# Page04_CPU_PWR.net
KiCad netlist of a schematic drawn in Altium Designer
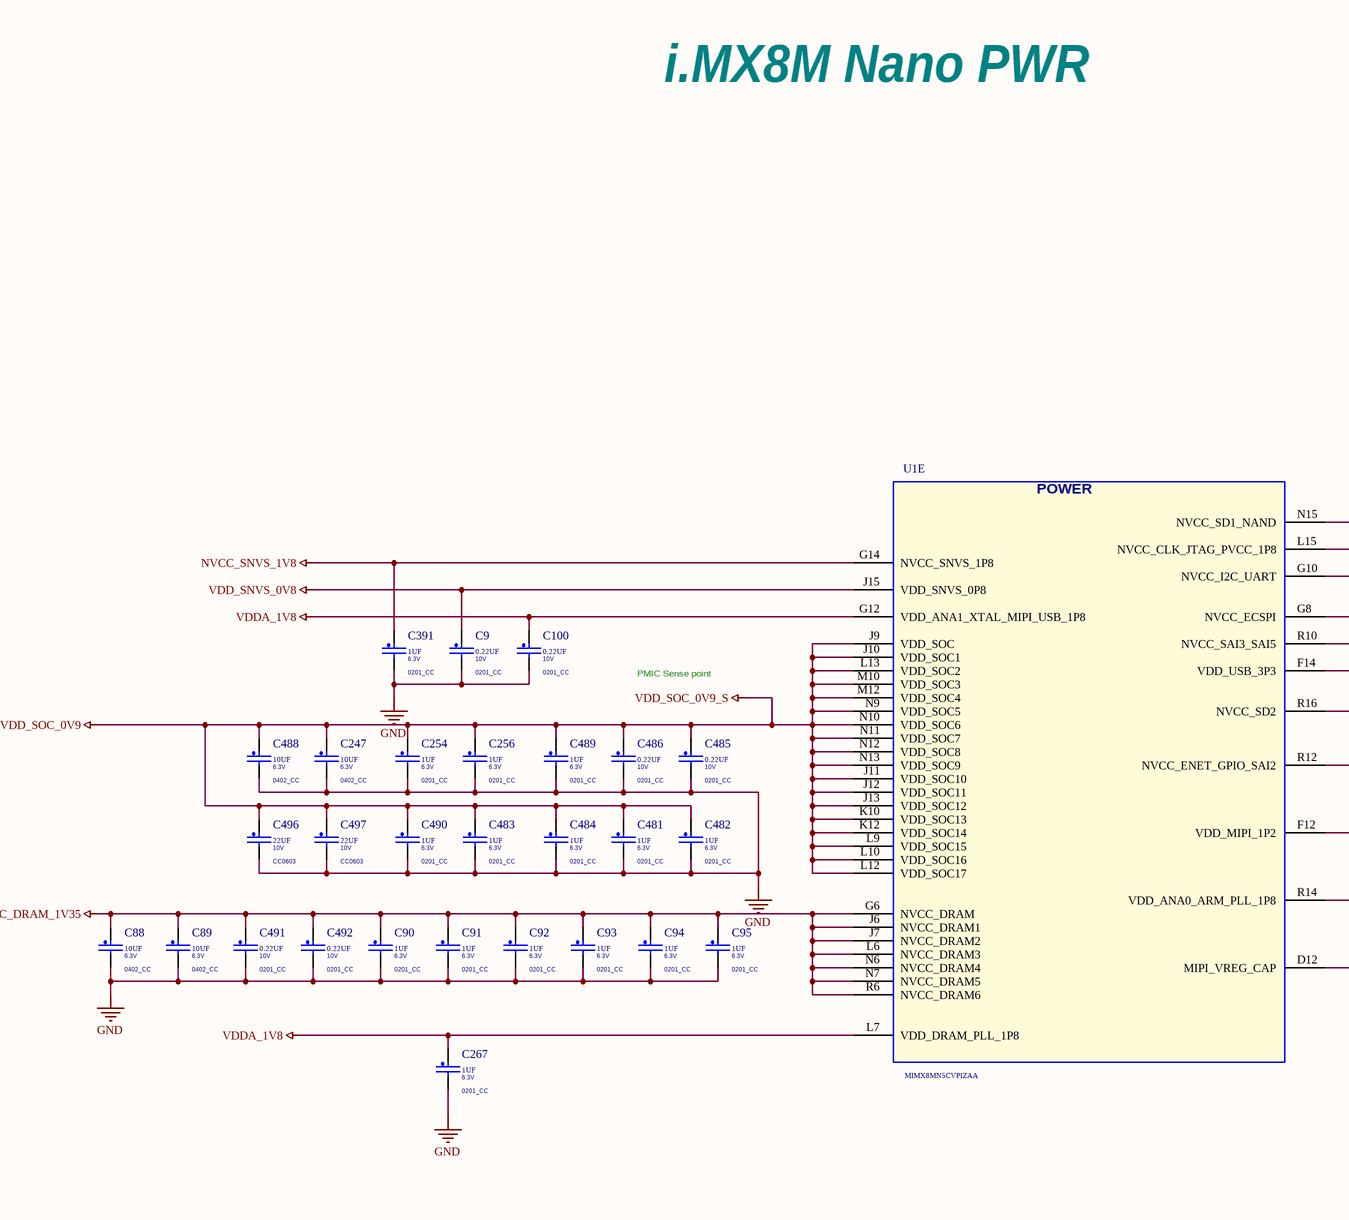
[diagram p0: Page04 CPU PWR.SchDoc, left]
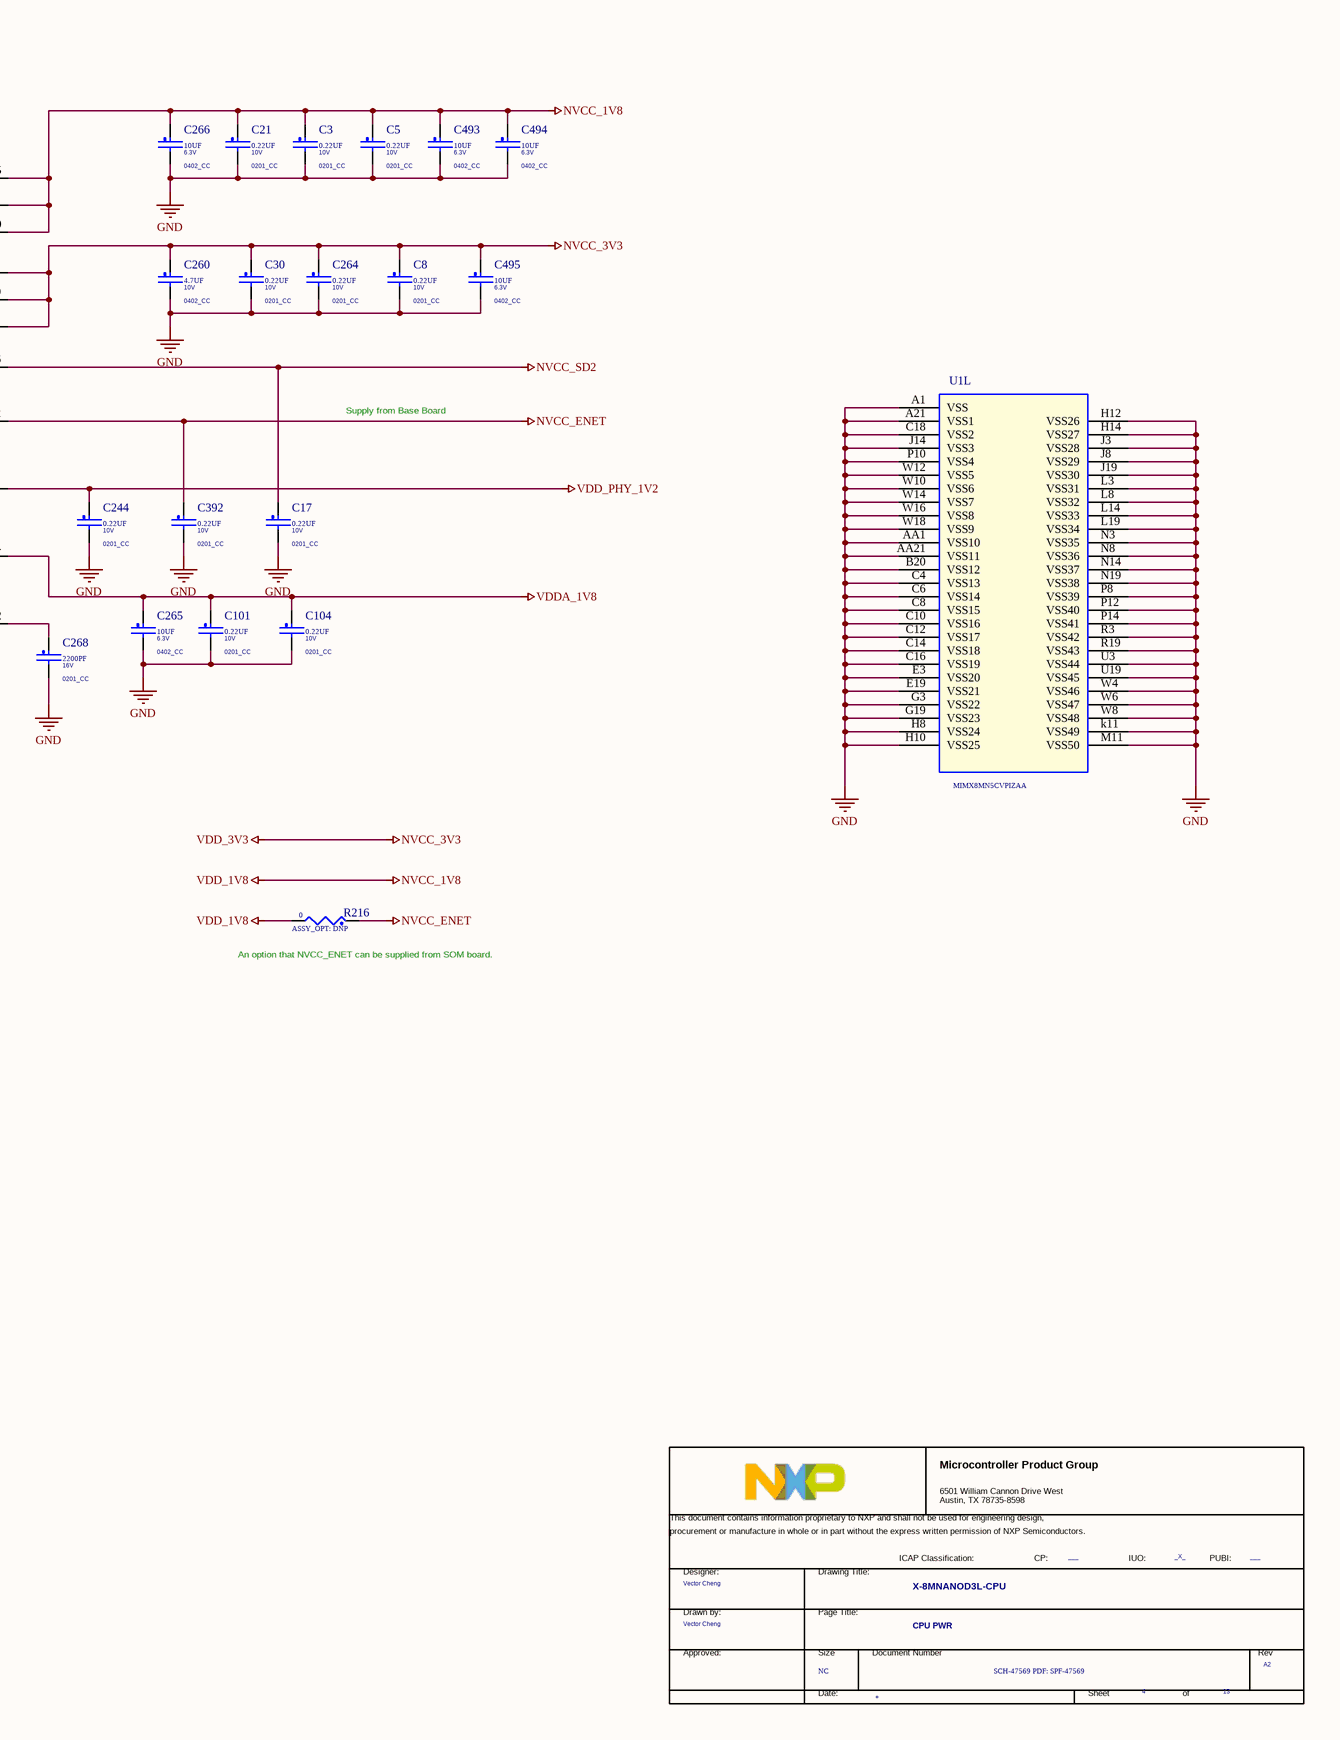
[diagram p1: Page04 CPU PWR.SchDoc, right]

(export (version "E")
  (design (tool "Eeschema 10.0.6"))
  (components
    (comp (ref "C3")
      (value "0.22UF")
      (footprint "0201_CC - C")
      (description "CAP CER 0.22UF 10V 20% X5R 0201")
      (fields
        (field (name "VOLTAGE") "10V")
        (field (name "TOLERANCE") "20%")
        (field (name "PCB FOOTPRINT") "0201_CC")
      )
      (libsource (lib "*") (part "CAP_NP"))
    )
    (comp (ref "C5")
      (value "0.22UF")
      (footprint "0201_CC - C")
      (description "CAP CER 0.22UF 10V 20% X5R 0201")
      (fields
        (field (name "TOLERANCE") "20%")
        (field (name "VOLTAGE") "10V")
        (field (name "PCB FOOTPRINT") "0201_CC")
      )
      (libsource (lib "*") (part "CAP_NP"))
    )
    (comp (ref "C8")
      (value "0.22UF")
      (footprint "0201_CC - C")
      (description "CAP CER 0.22UF 10V 20% X5R 0201")
      (fields
        (field (name "TOLERANCE") "20%")
        (field (name "VOLTAGE") "10V")
        (field (name "PCB FOOTPRINT") "0201_CC")
      )
      (libsource (lib "*") (part "CAP_NP"))
    )
    (comp (ref "C9")
      (value "0.22UF")
      (footprint "0201_CC - C")
      (description "CAP CER 0.22UF 10V 20% X5R 0201")
      (fields
        (field (name "VOLTAGE") "10V")
        (field (name "TOLERANCE") "20%")
        (field (name "PCB FOOTPRINT") "0201_CC")
      )
      (libsource (lib "*") (part "CAP_NP"))
    )
    (comp (ref "C17")
      (value "0.22UF")
      (footprint "0201_CC - C")
      (description "CAP CER 0.22UF 10V 20% X5R 0201")
      (fields
        (field (name "TOLERANCE") "20%")
        (field (name "VOLTAGE") "10V")
        (field (name "PCB FOOTPRINT") "0201_CC")
      )
      (libsource (lib "*") (part "CAP_NP"))
    )
    (comp (ref "C21")
      (value "0.22UF")
      (footprint "0201_CC - C")
      (description "CAP CER 0.22UF 10V 20% X5R 0201")
      (fields
        (field (name "TOLERANCE") "20%")
        (field (name "VOLTAGE") "10V")
        (field (name "PCB FOOTPRINT") "0201_CC")
      )
      (libsource (lib "*") (part "CAP_NP"))
    )
    (comp (ref "C30")
      (value "0.22UF")
      (footprint "0201_CC - C")
      (description "CAP CER 0.22UF 10V 20% X5R 0201")
      (fields
        (field (name "VOLTAGE") "10V")
        (field (name "TOLERANCE") "20%")
        (field (name "PCB FOOTPRINT") "0201_CC")
      )
      (libsource (lib "*") (part "CAP_NP"))
    )
    (comp (ref "C88")
      (value "10UF")
      (footprint "0402_CC - C")
      (description "CAP CER 10UF 6.3V 20% X5R 0402")
      (fields
        (field (name "PCB FOOTPRINT") "0402_CC")
        (field (name "TOLERANCE") "20%")
        (field (name "VOLTAGE") "6.3V")
      )
      (libsource (lib "*") (part "CAP_NP"))
    )
    (comp (ref "C89")
      (value "10UF")
      (footprint "0402_CC - C")
      (description "CAP CER 10UF 6.3V 20% X5R 0402")
      (fields
        (field (name "PCB FOOTPRINT") "0402_CC")
        (field (name "VOLTAGE") "6.3V")
        (field (name "TOLERANCE") "20%")
      )
      (libsource (lib "*") (part "CAP_NP"))
    )
    (comp (ref "C90")
      (value "1UF")
      (footprint "0201_CC - C")
      (description "CAP CER 1uF 6.3V 20% X5R 0201")
      (fields
        (field (name "PCB FOOTPRINT") "0201_CC")
        (field (name "VOLTAGE") "6.3V")
        (field (name "TOLERANCE") "20%")
      )
      (libsource (lib "*") (part "CAP_NP"))
    )
    (comp (ref "C91")
      (value "1UF")
      (footprint "0201_CC - C")
      (description "CAP CER 1uF 6.3V 20% X5R 0201")
      (fields
        (field (name "PCB FOOTPRINT") "0201_CC")
        (field (name "VOLTAGE") "6.3V")
        (field (name "TOLERANCE") "20%")
      )
      (libsource (lib "*") (part "CAP_NP"))
    )
    (comp (ref "C92")
      (value "1UF")
      (footprint "0201_CC - C")
      (description "CAP CER 1uF 6.3V 20% X5R 0201")
      (fields
        (field (name "PCB FOOTPRINT") "0201_CC")
        (field (name "VOLTAGE") "6.3V")
        (field (name "TOLERANCE") "20%")
      )
      (libsource (lib "*") (part "CAP_NP"))
    )
    (comp (ref "C93")
      (value "1UF")
      (footprint "0201_CC - C")
      (description "CAP CER 1uF 6.3V 20% X5R 0201")
      (fields
        (field (name "PCB FOOTPRINT") "0201_CC")
        (field (name "TOLERANCE") "20%")
        (field (name "VOLTAGE") "6.3V")
      )
      (libsource (lib "*") (part "CAP_NP"))
    )
    (comp (ref "C94")
      (value "1UF")
      (footprint "0201_CC - C")
      (description "CAP CER 1uF 6.3V 20% X5R 0201")
      (fields
        (field (name "PCB FOOTPRINT") "0201_CC")
        (field (name "TOLERANCE") "20%")
        (field (name "VOLTAGE") "6.3V")
      )
      (libsource (lib "*") (part "CAP_NP"))
    )
    (comp (ref "C95")
      (value "1UF")
      (footprint "0201_CC - C")
      (description "CAP CER 1uF 6.3V 20% X5R 0201")
      (fields
        (field (name "PCB FOOTPRINT") "0201_CC")
        (field (name "VOLTAGE") "6.3V")
        (field (name "TOLERANCE") "20%")
      )
      (libsource (lib "*") (part "CAP_NP"))
    )
    (comp (ref "C100")
      (value "0.22UF")
      (footprint "0201_CC - C")
      (description "CAP CER 0.22UF 10V 20% X5R 0201")
      (fields
        (field (name "TOLERANCE") "20%")
        (field (name "VOLTAGE") "10V")
        (field (name "PCB FOOTPRINT") "0201_CC")
      )
      (libsource (lib "*") (part "CAP_NP"))
    )
    (comp (ref "C101")
      (value "0.22UF")
      (footprint "0201_CC - C")
      (description "CAP CER 0.22UF 10V 20% X5R 0201")
      (fields
        (field (name "TOLERANCE") "20%")
        (field (name "VOLTAGE") "10V")
        (field (name "PCB FOOTPRINT") "0201_CC")
      )
      (libsource (lib "*") (part "CAP_NP"))
    )
    (comp (ref "C104")
      (value "0.22UF")
      (footprint "0201_CC - C")
      (description "CAP CER 0.22UF 10V 20% X5R 0201")
      (fields
        (field (name "VOLTAGE") "10V")
        (field (name "TOLERANCE") "20%")
        (field (name "PCB FOOTPRINT") "0201_CC")
      )
      (libsource (lib "*") (part "CAP_NP"))
    )
    (comp (ref "C244")
      (value "0.22UF")
      (footprint "0201_CC - C")
      (description "CAP CER 0.22UF 10V 20% X5R 0201")
      (fields
        (field (name "VOLTAGE") "10V")
        (field (name "TOLERANCE") "20%")
        (field (name "PCB FOOTPRINT") "0201_CC")
      )
      (libsource (lib "*") (part "CAP_NP"))
    )
    (comp (ref "C247")
      (value "10UF")
      (footprint "0402_CC - C")
      (description "CAP CER 10UF 6.3V 20% X5R 0402")
      (fields
        (field (name "VOLTAGE") "6.3V")
        (field (name "TOLERANCE") "20%")
        (field (name "PCB FOOTPRINT") "0402_CC")
      )
      (libsource (lib "*") (part "CAP_NP"))
    )
    (comp (ref "C254")
      (value "1UF")
      (footprint "0201_CC - C")
      (description "CAP CER 1uF 6.3V 20% X5R 0201")
      (fields
        (field (name "VOLTAGE") "6.3V")
        (field (name "TOLERANCE") "20%")
        (field (name "PCB FOOTPRINT") "0201_CC")
      )
      (libsource (lib "*") (part "CAP_NP"))
    )
    (comp (ref "C256")
      (value "1UF")
      (footprint "0201_CC - C")
      (description "CAP CER 1uF 6.3V 20% X5R 0201")
      (fields
        (field (name "TOLERANCE") "20%")
        (field (name "VOLTAGE") "6.3V")
        (field (name "PCB FOOTPRINT") "0201_CC")
      )
      (libsource (lib "*") (part "CAP_NP"))
    )
    (comp (ref "C260")
      (value "4.7UF")
      (footprint "0402_CC - C")
      (description "CAP CER 4.7uF 10V 10% X5R 0402")
      (fields
        (field (name "TOLERANCE") "10%")
        (field (name "VOLTAGE") "10V")
        (field (name "PCB FOOTPRINT") "0402_CC")
      )
      (libsource (lib "*") (part "CAP_NP"))
    )
    (comp (ref "C264")
      (value "0.22UF")
      (footprint "0201_CC - C")
      (description "CAP CER 0.22UF 10V 20% X5R 0201")
      (fields
        (field (name "TOLERANCE") "20%")
        (field (name "VOLTAGE") "10V")
        (field (name "PCB FOOTPRINT") "0201_CC")
      )
      (libsource (lib "*") (part "CAP_NP"))
    )
    (comp (ref "C265")
      (value "10UF")
      (footprint "0402_CC - C")
      (description "CAP CER 10UF 6.3V 20% X5R 0402")
      (fields
        (field (name "TOLERANCE") "20%")
        (field (name "VOLTAGE") "6.3V")
        (field (name "PCB FOOTPRINT") "0402_CC")
      )
      (libsource (lib "*") (part "CAP_NP"))
    )
    (comp (ref "C266")
      (value "10UF")
      (footprint "0402_CC - C")
      (description "CAP CER 10UF 6.3V 20% X5R 0402")
      (fields
        (field (name "TOLERANCE") "20%")
        (field (name "VOLTAGE") "6.3V")
        (field (name "PCB FOOTPRINT") "0402_CC")
      )
      (libsource (lib "*") (part "CAP_NP"))
    )
    (comp (ref "C267")
      (value "1UF")
      (footprint "0201_CC - C")
      (description "CAP CER 1uF 6.3V 20% X5R 0201")
      (fields
        (field (name "TOLERANCE") "20%")
        (field (name "VOLTAGE") "6.3V")
        (field (name "PCB FOOTPRINT") "0201_CC")
      )
      (libsource (lib "*") (part "CAP_NP"))
    )
    (comp (ref "C268")
      (value "2200PF")
      (footprint "0201_CC - C")
      (description "CAP CER 2200PF 16V 10% X7R 0201")
      (fields
        (field (name "TOLERANCE") "20%")
        (field (name "VOLTAGE") "16V")
        (field (name "PCB FOOTPRINT") "0201_CC")
      )
      (libsource (lib "*") (part "CAP_NP"))
    )
    (comp (ref "C391")
      (value "1UF")
      (footprint "0201_CC - C")
      (description "CAP CER 1uF 6.3V 20% X5R 0201")
      (fields
        (field (name "TOLERANCE") "20%")
        (field (name "VOLTAGE") "6.3V")
        (field (name "PCB FOOTPRINT") "0201_CC")
      )
      (libsource (lib "*") (part "CAP_NP"))
    )
    (comp (ref "C392")
      (value "0.22UF")
      (footprint "0201_CC - C")
      (description "CAP CER 0.22UF 10V 20% X5R 0201")
      (fields
        (field (name "VOLTAGE") "10V")
        (field (name "TOLERANCE") "20%")
        (field (name "PCB FOOTPRINT") "0201_CC")
      )
      (libsource (lib "*") (part "CAP_NP"))
    )
    (comp (ref "C481")
      (value "1UF")
      (footprint "0201_CC - C")
      (description "CAP CER 1uF 6.3V 20% X5R 0201")
      (fields
        (field (name "VOLTAGE") "6.3V")
        (field (name "TOLERANCE") "20%")
        (field (name "PCB FOOTPRINT") "0201_CC")
      )
      (libsource (lib "*") (part "CAP_NP"))
    )
    (comp (ref "C482")
      (value "1UF")
      (footprint "0201_CC - C")
      (description "CAP CER 1uF 6.3V 20% X5R 0201")
      (fields
        (field (name "VOLTAGE") "6.3V")
        (field (name "TOLERANCE") "20%")
        (field (name "PCB FOOTPRINT") "0201_CC")
      )
      (libsource (lib "*") (part "CAP_NP"))
    )
    (comp (ref "C483")
      (value "1UF")
      (footprint "0201_CC - C")
      (description "CAP CER 1uF 6.3V 20% X5R 0201")
      (fields
        (field (name "VOLTAGE") "6.3V")
        (field (name "TOLERANCE") "20%")
        (field (name "PCB FOOTPRINT") "0201_CC")
      )
      (libsource (lib "*") (part "CAP_NP"))
    )
    (comp (ref "C484")
      (value "1UF")
      (footprint "0201_CC - C")
      (description "CAP CER 1uF 6.3V 20% X5R 0201")
      (fields
        (field (name "VOLTAGE") "6.3V")
        (field (name "TOLERANCE") "20%")
        (field (name "PCB FOOTPRINT") "0201_CC")
      )
      (libsource (lib "*") (part "CAP_NP"))
    )
    (comp (ref "C485")
      (value "0.22UF")
      (footprint "0201_CC - C")
      (description "CAP CER 0.22UF 10V 20% X5R 0201")
      (fields
        (field (name "VOLTAGE") "10V")
        (field (name "TOLERANCE") "20%")
        (field (name "PCB FOOTPRINT") "0201_CC")
      )
      (libsource (lib "*") (part "CAP_NP"))
    )
    (comp (ref "C486")
      (value "0.22UF")
      (footprint "0201_CC - C")
      (description "CAP CER 0.22UF 10V 20% X5R 0201")
      (fields
        (field (name "VOLTAGE") "10V")
        (field (name "TOLERANCE") "20%")
        (field (name "PCB FOOTPRINT") "0201_CC")
      )
      (libsource (lib "*") (part "CAP_NP"))
    )
    (comp (ref "C488")
      (value "10UF")
      (footprint "0402_CC - C")
      (description "CAP CER 10UF 6.3V 20% X5R 0402")
      (fields
        (field (name "VOLTAGE") "6.3V")
        (field (name "TOLERANCE") "20%")
        (field (name "PCB FOOTPRINT") "0402_CC")
      )
      (libsource (lib "*") (part "CAP_NP"))
    )
    (comp (ref "C489")
      (value "1UF")
      (footprint "0201_CC - C")
      (description "CAP CER 1uF 6.3V 20% X5R 0201")
      (fields
        (field (name "VOLTAGE") "6.3V")
        (field (name "TOLERANCE") "20%")
        (field (name "PCB FOOTPRINT") "0201_CC")
      )
      (libsource (lib "*") (part "CAP_NP"))
    )
    (comp (ref "C490")
      (value "1UF")
      (footprint "0201_CC - C")
      (description "CAP CER 1uF 6.3V 20% X5R 0201")
      (fields
        (field (name "VOLTAGE") "6.3V")
        (field (name "TOLERANCE") "20%")
        (field (name "PCB FOOTPRINT") "0201_CC")
      )
      (libsource (lib "*") (part "CAP_NP"))
    )
    (comp (ref "C491")
      (value "0.22UF")
      (footprint "0201_CC - C")
      (description "CAP CER 0.22UF 10V 20% X5R 0201")
      (fields
        (field (name "PCB FOOTPRINT") "0201_CC")
        (field (name "TOLERANCE") "20%")
        (field (name "VOLTAGE") "10V")
      )
      (libsource (lib "*") (part "CAP_NP"))
    )
    (comp (ref "C492")
      (value "0.22UF")
      (footprint "0201_CC - C")
      (description "CAP CER 0.22UF 10V 20% X5R 0201")
      (fields
        (field (name "PCB FOOTPRINT") "0201_CC")
        (field (name "TOLERANCE") "20%")
        (field (name "VOLTAGE") "10V")
      )
      (libsource (lib "*") (part "CAP_NP"))
    )
    (comp (ref "C493")
      (value "10UF")
      (footprint "0402_CC - C")
      (description "CAP CER 10UF 6.3V 20% X5R 0402")
      (fields
        (field (name "TOLERANCE") "20%")
        (field (name "VOLTAGE") "6.3V")
        (field (name "PCB FOOTPRINT") "0402_CC")
      )
      (libsource (lib "*") (part "CAP_NP"))
    )
    (comp (ref "C494")
      (value "10UF")
      (footprint "0402_CC - C")
      (description "CAP CER 10UF 6.3V 20% X5R 0402")
      (fields
        (field (name "TOLERANCE") "20%")
        (field (name "VOLTAGE") "6.3V")
        (field (name "PCB FOOTPRINT") "0402_CC")
      )
      (libsource (lib "*") (part "CAP_NP"))
    )
    (comp (ref "C495")
      (value "10UF")
      (footprint "0402_CC - C")
      (description "CAP CER 10UF 6.3V 20% X5R 0402")
      (fields
        (field (name "VOLTAGE") "6.3V")
        (field (name "TOLERANCE") "20%")
        (field (name "PCB FOOTPRINT") "0402_CC")
      )
      (libsource (lib "*") (part "CAP_NP"))
    )
    (comp (ref "C496")
      (value "22UF")
      (footprint "0603_CC")
      (description "CAP CER 22uF 10V 20% X5R 0603")
      (fields
        (field (name "VOLTAGE") "10V")
        (field (name "TOLERANCE") "20%")
        (field (name "PCB FOOTPRINT") "CC0603")
      )
      (libsource (lib "*") (part "CAP_NP"))
    )
    (comp (ref "C497")
      (value "22UF")
      (footprint "0603_CC")
      (description "CAP CER 22uF 10V 20% X5R 0603")
      (fields
        (field (name "VOLTAGE") "10V")
        (field (name "TOLERANCE") "20%")
        (field (name "PCB FOOTPRINT") "CC0603")
      )
      (libsource (lib "*") (part "CAP_NP"))
    )
    (comp (ref "R216")
      (value "0")
      (footprint "0402_CC")
      (description "RES MF ZERO OHM 1/16W 5% 0402")
      (fields
        (field (name "ASSY_OPT") "DNP")
        (field (name "TOLERANCE") "5%")
        (field (name "VOLTAGE") "1/16W")
      )
      (libsource (lib "*") (part "RES"))
    )
    (comp (ref "U1")
      (value "MIMX8MN5CVPIZAA")
      (footprint "BGA306C50P21X21_1100X1100X101")
      (description "IC CPU QUAD CORTEX A53+M7 1.4GHZ -- BGA306")
      (libsource (lib "*") (part "MIMX8MN"))
    )
  )
  (nets
    (net (code "1") (name "GND") (class "Default")
      (node (ref "C100") (pin "2") (pinfunction "2_2") (pintype "passive"))
      (node (ref "C101") (pin "2") (pinfunction "2_2") (pintype "passive"))
      (node (ref "C104") (pin "2") (pinfunction "2_2") (pintype "passive"))
      (node (ref "C17") (pin "2") (pinfunction "2_2") (pintype "passive"))
      (node (ref "C21") (pin "2") (pinfunction "2_2") (pintype "passive"))
      (node (ref "C244") (pin "2") (pinfunction "2_2") (pintype "passive"))
      (node (ref "C247") (pin "2") (pinfunction "2_2") (pintype "passive"))
      (node (ref "C254") (pin "2") (pinfunction "2_2") (pintype "passive"))
      (node (ref "C256") (pin "2") (pinfunction "2_2") (pintype "passive"))
      (node (ref "C260") (pin "2") (pinfunction "2_2") (pintype "passive"))
      (node (ref "C264") (pin "2") (pinfunction "2_2") (pintype "passive"))
      (node (ref "C265") (pin "2") (pinfunction "2_2") (pintype "passive"))
      (node (ref "C266") (pin "2") (pinfunction "2_2") (pintype "passive"))
      (node (ref "C267") (pin "2") (pinfunction "2_2") (pintype "passive"))
      (node (ref "C268") (pin "2") (pinfunction "2_2") (pintype "passive"))
      (node (ref "C3") (pin "2") (pinfunction "2_2") (pintype "passive"))
      (node (ref "C30") (pin "2") (pinfunction "2_2") (pintype "passive"))
      (node (ref "C391") (pin "2") (pinfunction "2_2") (pintype "passive"))
      (node (ref "C392") (pin "2") (pinfunction "2_2") (pintype "passive"))
      (node (ref "C481") (pin "2") (pinfunction "2_2") (pintype "passive"))
      (node (ref "C482") (pin "2") (pinfunction "2_2") (pintype "passive"))
      (node (ref "C483") (pin "2") (pinfunction "2_2") (pintype "passive"))
      (node (ref "C484") (pin "2") (pinfunction "2_2") (pintype "passive"))
      (node (ref "C485") (pin "2") (pinfunction "2_2") (pintype "passive"))
      (node (ref "C486") (pin "2") (pinfunction "2_2") (pintype "passive"))
      (node (ref "C488") (pin "2") (pinfunction "2_2") (pintype "passive"))
      (node (ref "C489") (pin "2") (pinfunction "2_2") (pintype "passive"))
      (node (ref "C490") (pin "2") (pinfunction "2_2") (pintype "passive"))
      (node (ref "C491") (pin "2") (pinfunction "2_2") (pintype "passive"))
      (node (ref "C492") (pin "2") (pinfunction "2_2") (pintype "passive"))
      (node (ref "C493") (pin "2") (pinfunction "2_2") (pintype "passive"))
      (node (ref "C494") (pin "2") (pinfunction "2_2") (pintype "passive"))
      (node (ref "C495") (pin "2") (pinfunction "2_2") (pintype "passive"))
      (node (ref "C496") (pin "2") (pinfunction "2_2") (pintype "passive"))
      (node (ref "C497") (pin "2") (pinfunction "2_2") (pintype "passive"))
      (node (ref "C5") (pin "2") (pinfunction "2_2") (pintype "passive"))
      (node (ref "C8") (pin "2") (pinfunction "2_2") (pintype "passive"))
      (node (ref "C88") (pin "2") (pinfunction "2_2") (pintype "passive"))
      (node (ref "C89") (pin "2") (pinfunction "2_2") (pintype "passive"))
      (node (ref "C9") (pin "2") (pinfunction "2_2") (pintype "passive"))
      (node (ref "C90") (pin "2") (pinfunction "2_2") (pintype "passive"))
      (node (ref "C91") (pin "2") (pinfunction "2_2") (pintype "passive"))
      (node (ref "C92") (pin "2") (pinfunction "2_2") (pintype "passive"))
      (node (ref "C93") (pin "2") (pinfunction "2_2") (pintype "passive"))
      (node (ref "C94") (pin "2") (pinfunction "2_2") (pintype "passive"))
      (node (ref "C95") (pin "2") (pinfunction "2_2") (pintype "passive"))
      (node (ref "U1") (pin "A1") (pinfunction "VSS_A1") (pintype "passive"))
      (node (ref "U1") (pin "A21") (pinfunction "VSS1_A21") (pintype "passive"))
      (node (ref "U1") (pin "AA1") (pinfunction "VSS10_AA1") (pintype "passive"))
      (node (ref "U1") (pin "AA21") (pinfunction "VSS11_AA21") (pintype "passive"))
      (node (ref "U1") (pin "B20") (pinfunction "VSS12_B20") (pintype "passive"))
      (node (ref "U1") (pin "C10") (pinfunction "VSS16_C10") (pintype "passive"))
      (node (ref "U1") (pin "C12") (pinfunction "VSS17_C12") (pintype "passive"))
      (node (ref "U1") (pin "C14") (pinfunction "VSS18_C14") (pintype "passive"))
      (node (ref "U1") (pin "C16") (pinfunction "VSS19_C16") (pintype "passive"))
      (node (ref "U1") (pin "C18") (pinfunction "VSS2_C18") (pintype "passive"))
      (node (ref "U1") (pin "C4") (pinfunction "VSS13_C4") (pintype "passive"))
      (node (ref "U1") (pin "C6") (pinfunction "VSS14_C6") (pintype "passive"))
      (node (ref "U1") (pin "C8") (pinfunction "VSS15_C8") (pintype "passive"))
      (node (ref "U1") (pin "E19") (pinfunction "VSS21_E19") (pintype "passive"))
      (node (ref "U1") (pin "E3") (pinfunction "VSS20_E3") (pintype "passive"))
      (node (ref "U1") (pin "G19") (pinfunction "VSS23_G19") (pintype "passive"))
      (node (ref "U1") (pin "G3") (pinfunction "VSS22_G3") (pintype "passive"))
      (node (ref "U1") (pin "H10") (pinfunction "VSS25_H10") (pintype "passive"))
      (node (ref "U1") (pin "H12") (pinfunction "VSS26_H12") (pintype "passive"))
      (node (ref "U1") (pin "H14") (pinfunction "VSS27_H14") (pintype "passive"))
      (node (ref "U1") (pin "H8") (pinfunction "VSS24_H8") (pintype "passive"))
      (node (ref "U1") (pin "J14") (pinfunction "VSS3_J14") (pintype "passive"))
      (node (ref "U1") (pin "J19") (pinfunction "VSS30_J19") (pintype "passive"))
      (node (ref "U1") (pin "J3") (pinfunction "VSS28_J3") (pintype "passive"))
      (node (ref "U1") (pin "J8") (pinfunction "VSS29_J8") (pintype "passive"))
      (node (ref "U1") (pin "L14") (pinfunction "VSS33_L14") (pintype "passive"))
      (node (ref "U1") (pin "L19") (pinfunction "VSS34_L19") (pintype "passive"))
      (node (ref "U1") (pin "L3") (pinfunction "VSS31_L3") (pintype "passive"))
      (node (ref "U1") (pin "L8") (pinfunction "VSS32_L8") (pintype "passive"))
      (node (ref "U1") (pin "M11") (pinfunction "VSS50_M11") (pintype "passive"))
      (node (ref "U1") (pin "N14") (pinfunction "VSS37_N14") (pintype "passive"))
      (node (ref "U1") (pin "N19") (pinfunction "VSS38_N19") (pintype "passive"))
      (node (ref "U1") (pin "N3") (pinfunction "VSS35_N3") (pintype "passive"))
      (node (ref "U1") (pin "N8") (pinfunction "VSS36_N8") (pintype "passive"))
      (node (ref "U1") (pin "P10") (pinfunction "VSS4_P10") (pintype "passive"))
      (node (ref "U1") (pin "P12") (pinfunction "VSS40_P12") (pintype "passive"))
      (node (ref "U1") (pin "P14") (pinfunction "VSS41_P14") (pintype "passive"))
      (node (ref "U1") (pin "P8") (pinfunction "VSS39_P8") (pintype "passive"))
      (node (ref "U1") (pin "R19") (pinfunction "VSS43_R19") (pintype "passive"))
      (node (ref "U1") (pin "R3") (pinfunction "VSS42_R3") (pintype "passive"))
      (node (ref "U1") (pin "U19") (pinfunction "VSS45_U19") (pintype "passive"))
      (node (ref "U1") (pin "U3") (pinfunction "VSS44_U3") (pintype "passive"))
      (node (ref "U1") (pin "W10") (pinfunction "VSS6_W10") (pintype "passive"))
      (node (ref "U1") (pin "W12") (pinfunction "VSS5_W12") (pintype "passive"))
      (node (ref "U1") (pin "W14") (pinfunction "VSS7_W14") (pintype "passive"))
      (node (ref "U1") (pin "W16") (pinfunction "VSS8_W16") (pintype "passive"))
      (node (ref "U1") (pin "W18") (pinfunction "VSS9_W18") (pintype "passive"))
      (node (ref "U1") (pin "W4") (pinfunction "VSS46_W4") (pintype "passive"))
      (node (ref "U1") (pin "W6") (pinfunction "VSS47_W6") (pintype "passive"))
      (node (ref "U1") (pin "W8") (pinfunction "VSS48_W8") (pintype "passive"))
      (node (ref "U1") (pin "k11") (pinfunction "VSS49_k11") (pintype "passive"))
    )
    (net (code "2") (name "NVCC_1V8") (class "Default")
      (node (ref "C21") (pin "1") (pinfunction "1_1") (pintype "passive"))
      (node (ref "C266") (pin "1") (pinfunction "1_1") (pintype "passive"))
      (node (ref "C3") (pin "1") (pinfunction "1_1") (pintype "passive"))
      (node (ref "C493") (pin "1") (pinfunction "1_1") (pintype "passive"))
      (node (ref "C494") (pin "1") (pinfunction "1_1") (pintype "passive"))
      (node (ref "C5") (pin "1") (pinfunction "1_1") (pintype "passive"))
      (node (ref "R216") (pin "2") (pinfunction "2_2") (pintype "passive"))
      (node (ref "U1") (pin "G10") (pinfunction "NVCC_I2C_UART_G10") (pintype "passive"))
      (node (ref "U1") (pin "L15") (pinfunction "NVCC_CLK_JTAG_PVCC_1P8_L15") (pintype "passive"))
      (node (ref "U1") (pin "N15") (pinfunction "NVCC_SD1_NAND_N15") (pintype "passive"))
    )
    (net (code "3") (name "NVCC_3V3") (class "Default")
      (node (ref "C260") (pin "1") (pinfunction "1_1") (pintype "passive"))
      (node (ref "C264") (pin "1") (pinfunction "1_1") (pintype "passive"))
      (node (ref "C30") (pin "1") (pinfunction "1_1") (pintype "passive"))
      (node (ref "C495") (pin "1") (pinfunction "1_1") (pintype "passive"))
      (node (ref "C8") (pin "1") (pinfunction "1_1") (pintype "passive"))
      (node (ref "U1") (pin "F14") (pinfunction "VDD_USB_3P3_F14") (pintype "passive"))
      (node (ref "U1") (pin "G8") (pinfunction "NVCC_ECSPI_G8") (pintype "passive"))
      (node (ref "U1") (pin "R10") (pinfunction "NVCC_SAI3_SAI5_R10") (pintype "passive"))
    )
    (net (code "4") (name "NVCC_DRAM_1V35") (class "Default")
      (node (ref "C491") (pin "1") (pinfunction "1_1") (pintype "passive"))
      (node (ref "C492") (pin "1") (pinfunction "1_1") (pintype "passive"))
      (node (ref "C88") (pin "1") (pinfunction "1_1") (pintype "passive"))
      (node (ref "C89") (pin "1") (pinfunction "1_1") (pintype "passive"))
      (node (ref "C90") (pin "1") (pinfunction "1_1") (pintype "passive"))
      (node (ref "C91") (pin "1") (pinfunction "1_1") (pintype "passive"))
      (node (ref "C92") (pin "1") (pinfunction "1_1") (pintype "passive"))
      (node (ref "C93") (pin "1") (pinfunction "1_1") (pintype "passive"))
      (node (ref "C94") (pin "1") (pinfunction "1_1") (pintype "passive"))
      (node (ref "C95") (pin "1") (pinfunction "1_1") (pintype "passive"))
      (node (ref "U1") (pin "G6") (pinfunction "NVCC_DRAM_G6") (pintype "passive"))
      (node (ref "U1") (pin "J6") (pinfunction "NVCC_DRAM1_J6") (pintype "passive"))
      (node (ref "U1") (pin "J7") (pinfunction "NVCC_DRAM2_J7") (pintype "passive"))
      (node (ref "U1") (pin "L6") (pinfunction "NVCC_DRAM3_L6") (pintype "passive"))
      (node (ref "U1") (pin "N6") (pinfunction "NVCC_DRAM4_N6") (pintype "passive"))
      (node (ref "U1") (pin "N7") (pinfunction "NVCC_DRAM5_N7") (pintype "passive"))
      (node (ref "U1") (pin "R6") (pinfunction "NVCC_DRAM6_R6") (pintype "passive"))
    )
    (net (code "5") (name "NVCC_ENET") (class "Default")
      (node (ref "C392") (pin "1") (pinfunction "1_1") (pintype "passive"))
      (node (ref "R216") (pin "1") (pinfunction "1_1") (pintype "passive"))
      (node (ref "U1") (pin "R12") (pinfunction "NVCC_ENET_GPIO_SAI2_R12") (pintype "passive"))
    )
    (net (code "6") (name "NVCC_SD2") (class "Default")
      (node (ref "C17") (pin "1") (pinfunction "1_1") (pintype "passive"))
      (node (ref "U1") (pin "R16") (pinfunction "NVCC_SD2_R16") (pintype "passive"))
    )
    (net (code "7") (name "NVCC_SNVS_1V8") (class "Default")
      (node (ref "C391") (pin "1") (pinfunction "1_1") (pintype "passive"))
      (node (ref "U1") (pin "G14") (pinfunction "NVCC_SNVS_1P8_G14") (pintype "passive"))
    )
    (net (code "8") (name "Net-(U1E-MIPI_VREG_CAP)") (class "Default")
      (node (ref "C268") (pin "1") (pinfunction "1_1") (pintype "passive"))
      (node (ref "U1") (pin "D12") (pinfunction "MIPI_VREG_CAP_D12") (pintype "passive"))
    )
    (net (code "9") (name "VDDA_1V8") (class "Default")
      (node (ref "C100") (pin "1") (pinfunction "1_1") (pintype "passive"))
      (node (ref "C101") (pin "1") (pinfunction "1_1") (pintype "passive"))
      (node (ref "C104") (pin "1") (pinfunction "1_1") (pintype "passive"))
      (node (ref "C265") (pin "1") (pinfunction "1_1") (pintype "passive"))
      (node (ref "C267") (pin "1") (pinfunction "1_1") (pintype "passive"))
      (node (ref "U1") (pin "G12") (pinfunction "VDD_ANA1_XTAL_MIPI_USB_1P8_G12") (pintype "passive"))
      (node (ref "U1") (pin "L7") (pinfunction "VDD_DRAM_PLL_1P8_L7") (pintype "passive"))
      (node (ref "U1") (pin "R14") (pinfunction "VDD_ANA0_ARM_PLL_1P8_R14") (pintype "passive"))
    )
    (net (code "10") (name "VDD_PHY_1V2") (class "Default")
      (node (ref "C244") (pin "1") (pinfunction "1_1") (pintype "passive"))
      (node (ref "U1") (pin "F12") (pinfunction "VDD_MIPI_1P2_F12") (pintype "passive"))
    )
    (net (code "11") (name "VDD_SNVS_0V8") (class "Default")
      (node (ref "C9") (pin "1") (pinfunction "1_1") (pintype "passive"))
      (node (ref "U1") (pin "J15") (pinfunction "VDD_SNVS_0P8_J15") (pintype "passive"))
    )
    (net (code "12") (name "VDD_SOC_0V9") (class "Default")
      (node (ref "C247") (pin "1") (pinfunction "1_1") (pintype "passive"))
      (node (ref "C254") (pin "1") (pinfunction "1_1") (pintype "passive"))
      (node (ref "C256") (pin "1") (pinfunction "1_1") (pintype "passive"))
      (node (ref "C481") (pin "1") (pinfunction "1_1") (pintype "passive"))
      (node (ref "C482") (pin "1") (pinfunction "1_1") (pintype "passive"))
      (node (ref "C483") (pin "1") (pinfunction "1_1") (pintype "passive"))
      (node (ref "C484") (pin "1") (pinfunction "1_1") (pintype "passive"))
      (node (ref "C485") (pin "1") (pinfunction "1_1") (pintype "passive"))
      (node (ref "C486") (pin "1") (pinfunction "1_1") (pintype "passive"))
      (node (ref "C488") (pin "1") (pinfunction "1_1") (pintype "passive"))
      (node (ref "C489") (pin "1") (pinfunction "1_1") (pintype "passive"))
      (node (ref "C490") (pin "1") (pinfunction "1_1") (pintype "passive"))
      (node (ref "C496") (pin "1") (pinfunction "1_1") (pintype "passive"))
      (node (ref "C497") (pin "1") (pinfunction "1_1") (pintype "passive"))
      (node (ref "U1") (pin "J10") (pinfunction "VDD_SOC1_J10") (pintype "passive"))
      (node (ref "U1") (pin "J11") (pinfunction "VDD_SOC10_J11") (pintype "passive"))
      (node (ref "U1") (pin "J12") (pinfunction "VDD_SOC11_J12") (pintype "passive"))
      (node (ref "U1") (pin "J13") (pinfunction "VDD_SOC12_J13") (pintype "passive"))
      (node (ref "U1") (pin "J9") (pinfunction "VDD_SOC_J9") (pintype "passive"))
      (node (ref "U1") (pin "K10") (pinfunction "VDD_SOC13_K10") (pintype "passive"))
      (node (ref "U1") (pin "K12") (pinfunction "VDD_SOC14_K12") (pintype "passive"))
      (node (ref "U1") (pin "L10") (pinfunction "VDD_SOC16_L10") (pintype "passive"))
      (node (ref "U1") (pin "L12") (pinfunction "VDD_SOC17_L12") (pintype "passive"))
      (node (ref "U1") (pin "L13") (pinfunction "VDD_SOC2_L13") (pintype "passive"))
      (node (ref "U1") (pin "L9") (pinfunction "VDD_SOC15_L9") (pintype "passive"))
      (node (ref "U1") (pin "M10") (pinfunction "VDD_SOC3_M10") (pintype "passive"))
      (node (ref "U1") (pin "M12") (pinfunction "VDD_SOC4_M12") (pintype "passive"))
      (node (ref "U1") (pin "N10") (pinfunction "VDD_SOC6_N10") (pintype "passive"))
      (node (ref "U1") (pin "N11") (pinfunction "VDD_SOC7_N11") (pintype "passive"))
      (node (ref "U1") (pin "N12") (pinfunction "VDD_SOC8_N12") (pintype "passive"))
      (node (ref "U1") (pin "N13") (pinfunction "VDD_SOC9_N13") (pintype "passive"))
      (node (ref "U1") (pin "N9") (pinfunction "VDD_SOC5_N9") (pintype "passive"))
    )
  )
)
